# SIMCOM-SIM39EA-MALE.net
KiCad netlist of a schematic drawn in EAGLE
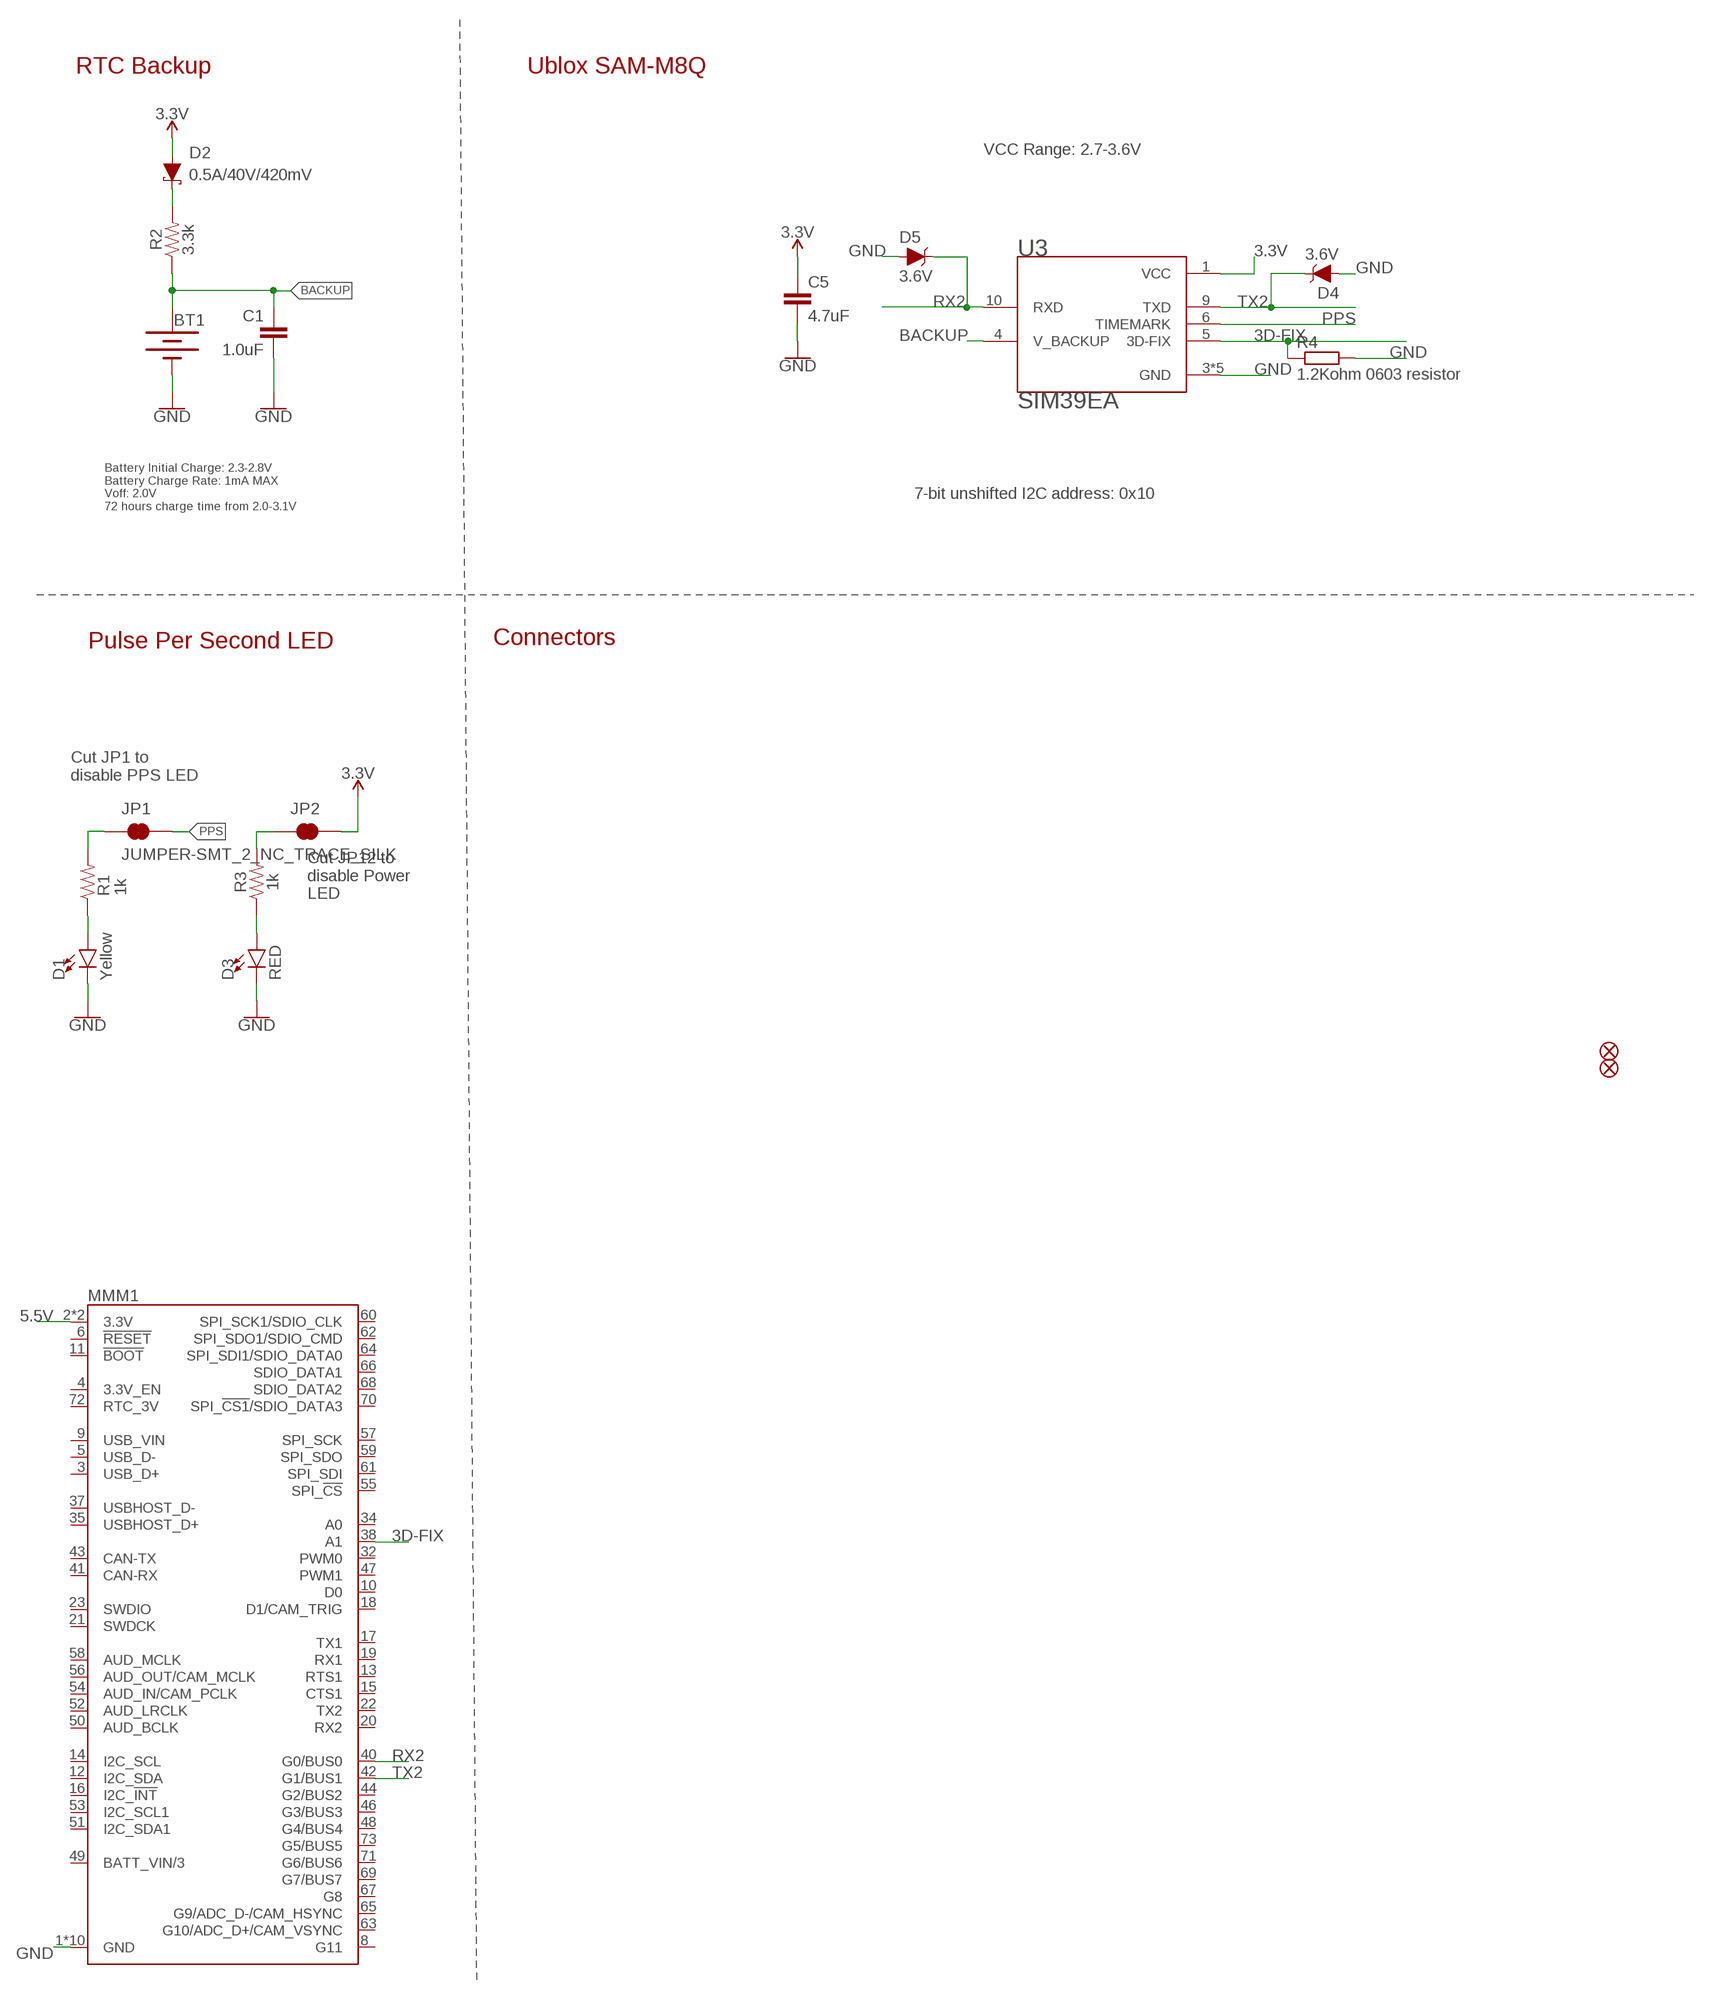
[diagram p0: schematic, sheet 1]
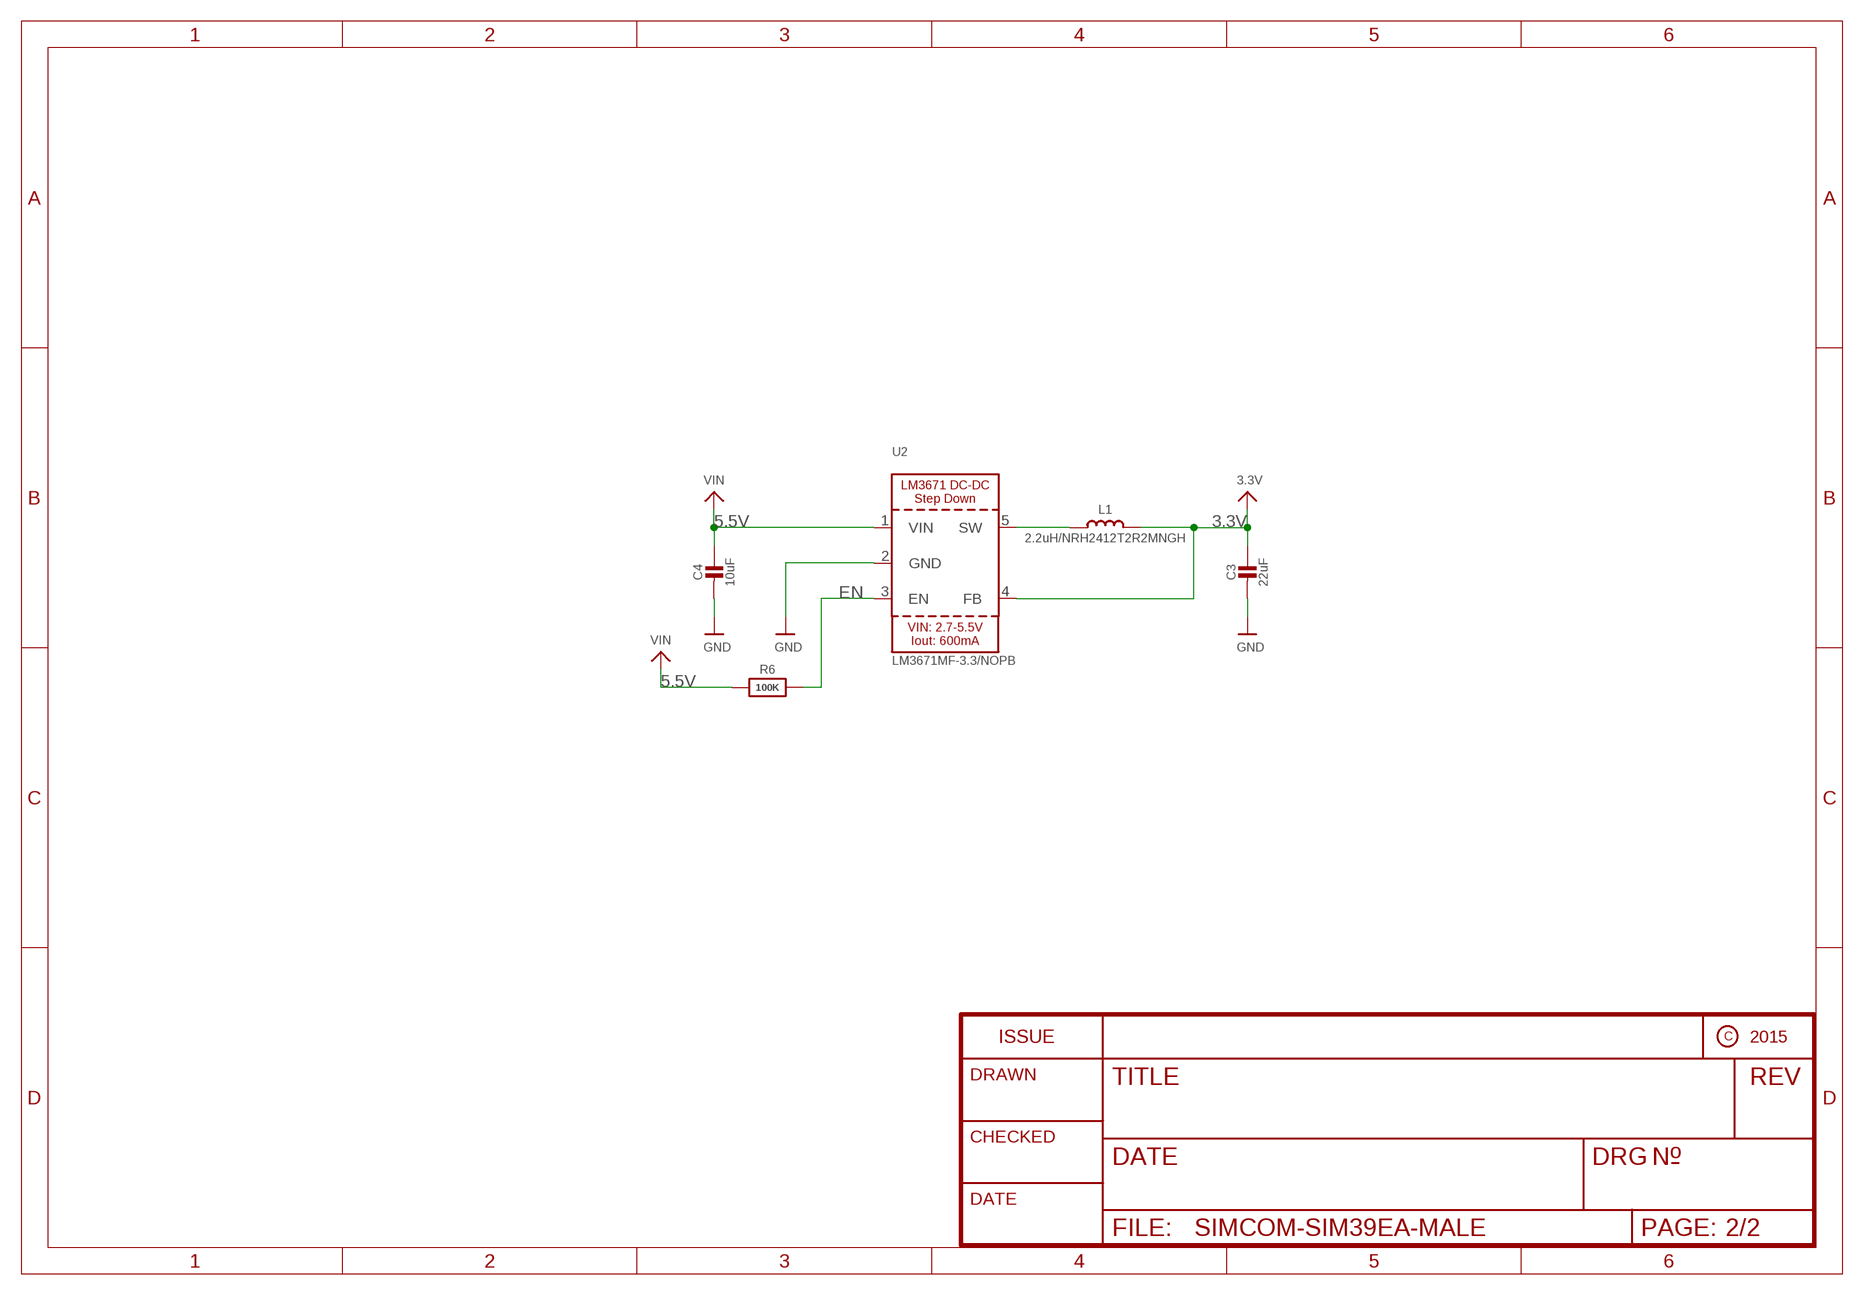
[diagram p1: schematic, sheet 2]

(export (version "E")
  (design (tool "Eeschema 10.0.6"))
  (components
    (comp (ref "BT1")
      (value "6.8MM_COIN_CELL")
      (footprint "eagle-import:ML414H_IV01E")
      (libsource (lib "eagle-import") (part "ML414H_IV01E_BATTERY"))
    )
    (comp (ref "C1")
      (value "1.0uF")
      (footprint "eagle-import:0603")
      (libsource (lib "eagle-import") (part "1.0UF-0603-16V-10%"))
    )
    (comp (ref "C5")
      (value "4.7uF")
      (footprint "eagle-import:0402-TIGHT")
      (libsource (lib "eagle-import") (part "4.7UF-0402_TIGHT-6.3V-20%-X5R"))
    )
    (comp (ref "D1")
      (value "Yellow")
      (footprint "eagle-import:LED-0603")
      (libsource (lib "eagle-import") (part "LED-YELLOW0603"))
    )
    (comp (ref "D2")
      (value "0.5A/40V/420mV")
      (footprint "eagle-import:SOD-323")
      (libsource (lib "eagle-import") (part "DIODE-SCHOTTKY-PMEG4005EJ"))
    )
    (comp (ref "D3")
      (value "RED")
      (footprint "eagle-import:LED-0603")
      (libsource (lib "eagle-import") (part "LED-RED0603"))
    )
    (comp (ref "D4")
      (value "3.6V")
      (footprint "eagle-import:SOD-323")
      (libsource (lib "eagle-import") (part "DIODE-ZENER-BZT52C3V6S"))
    )
    (comp (ref "D5")
      (value "3.6V")
      (footprint "eagle-import:SOD-323")
      (libsource (lib "eagle-import") (part "DIODE-ZENER-BZT52C3V6S"))
    )
    (comp (ref "FD3")
      (value "FIDUCIALUFIDUCIAL")
      (footprint "eagle-import:FIDUCIAL-MICRO")
      (libsource (lib "eagle-import") (part "FIDUCIALUFIDUCIAL"))
    )
    (comp (ref "FD4")
      (value "FIDUCIALUFIDUCIAL")
      (footprint "eagle-import:FIDUCIAL-MICRO")
      (libsource (lib "eagle-import") (part "FIDUCIALUFIDUCIAL"))
    )
    (comp (ref "JP1")
      (value "JUMPER-SMT_2_NC_TRACE_SILK")
      (footprint "eagle-import:SMT-JUMPER_2_NC_TRACE_SILK")
      (libsource (lib "eagle-import") (part "JUMPER-SMT_2_NC_TRACE_SILK"))
    )
    (comp (ref "JP2")
      (value "JUMPER-SMT_2_NC_TRACE_SILK")
      (footprint "eagle-import:SMT-JUMPER_2_NC_TRACE_SILK")
      (libsource (lib "eagle-import") (part "JUMPER-SMT_2_NC_TRACE_SILK"))
    )
    (comp (ref "MMM1")
      (value "MICROMOD_4222_MALE")
      (footprint "eagle-import:MICROMOD_4222_MALE")
      (libsource (lib "eagle-import") (part "MICROMOD_4222_MALE"))
    )
    (comp (ref "R1")
      (value "1k")
      (footprint "eagle-import:0603")
      (libsource (lib "eagle-import") (part "1KOHM-0603-1/10W-1%"))
    )
    (comp (ref "R2")
      (value "3.3k")
      (footprint "eagle-import:0603")
      (libsource (lib "eagle-import") (part "3.3KOHM-0603-1/10W-1%"))
    )
    (comp (ref "R3")
      (value "1k")
      (footprint "eagle-import:0603")
      (libsource (lib "eagle-import") (part "1KOHM-0603-1/10W-1%"))
    )
    (comp (ref "R4")
      (value "1.2Kohm 0603 resistor")
      (footprint "eagle-import:R603")
      (libsource (lib "eagle-import") (part "RESISTOR-0603"))
    )
    (comp (ref "U3")
      (value "SIM39EA")
      (footprint "eagle-import:DFN1600X1600X750-13N")
      (fields (field (name "MF") "Simcom"))
      (libsource (lib "eagle-import") (part "SIM39EA"))
    )
    (comp (ref "C3")
      (value "22uF")
      (footprint "eagle-import:0805-NO")
      (libsource (lib "eagle-import") (part "CAP_CERAMIC0805-NOOUTLINE"))
    )
    (comp (ref "C4")
      (value "10uF")
      (footprint "eagle-import:0805-NO")
      (libsource (lib "eagle-import") (part "CAP_CERAMIC0805-NOOUTLINE"))
    )
    (comp (ref "L1")
      (value "2.2uH/NRH2412T2R2MNGH")
      (footprint "eagle-import:INDUCTOR_TAIYOYUDEN_NRH2412T")
      (libsource (lib "eagle-import") (part "INDUCTORNRH2412T"))
    )
    (comp (ref "R6")
      (value "100K")
      (footprint "eagle-import:0805-NO")
      (libsource (lib "eagle-import") (part "RESISTOR0805_NOOUTLINE"))
    )
    (comp (ref "U2")
      (value "LM3671MF-3.3/NOPB")
      (footprint "eagle-import:SOT23-5")
      (libsource (lib "eagle-import") (part "VREG_LM3671"))
    )
  )
  (nets
    (net (code "1") (name "3.3V") (class "Default")
      (node (ref "C3") (pin "1") (pinfunction "1_1") (pintype "passive"))
      (node (ref "C5") (pin "1") (pinfunction "1_1") (pintype "passive"))
      (node (ref "D2") (pin "A") (pinfunction "A_A") (pintype "passive"))
      (node (ref "JP2") (pin "2") (pinfunction "2_2") (pintype "passive"))
      (node (ref "L1") (pin "2") (pinfunction "2_2") (pintype "passive"))
      (node (ref "U2") (pin "4") (pinfunction "FB_4") (pintype "power_in"))
      (node (ref "U3") (pin "1") (pinfunction "VCC_1") (pintype "power_in"))
    )
    (net (code "2") (name "3D-FIX") (class "Default")
      (node (ref "MMM1") (pin "38") (pinfunction "A1_38") (pintype "bidirectional"))
      (node (ref "R4") (pin "1") (pinfunction "1_1") (pintype "passive"))
      (node (ref "U3") (pin "5") (pinfunction "3D-FIX_5") (pintype "output"))
    )
    (net (code "3") (name "5.5V") (class "Default")
      (node (ref "C4") (pin "1") (pinfunction "1_1") (pintype "passive"))
      (node (ref "MMM1") (pin "2") (pinfunction "3.3V_2") (pintype "bidirectional"))
      (node (ref "MMM1") (pin "74") (pinfunction "3.3V_74") (pintype "bidirectional"))
      (node (ref "R6") (pin "1") (pinfunction "1_1") (pintype "passive"))
      (node (ref "U2") (pin "1") (pinfunction "VIN_1") (pintype "power_in"))
    )
    (net (code "4") (name "BACKUP") (class "Default")
      (node (ref "BT1") (pin "+") (pinfunction "+_+") (pintype "power_in"))
      (node (ref "C1") (pin "1") (pinfunction "1_1") (pintype "passive"))
      (node (ref "R2") (pin "1") (pinfunction "1_1") (pintype "passive"))
      (node (ref "U3") (pin "4") (pinfunction "V_BACKUP_4") (pintype "bidirectional"))
    )
    (net (code "5") (name "EN") (class "Default")
      (node (ref "R6") (pin "2") (pinfunction "2_2") (pintype "passive"))
      (node (ref "U2") (pin "3") (pinfunction "EN_3") (pintype "input"))
    )
    (net (code "6") (name "GND") (class "Default")
      (node (ref "BT1") (pin "-") (pinfunction "-_-") (pintype "power_in"))
      (node (ref "C1") (pin "2") (pinfunction "2_2") (pintype "passive"))
      (node (ref "C3") (pin "2") (pinfunction "2_2") (pintype "passive"))
      (node (ref "C4") (pin "2") (pinfunction "2_2") (pintype "passive"))
      (node (ref "C5") (pin "2") (pinfunction "2_2") (pintype "passive"))
      (node (ref "D1") (pin "C") (pinfunction "C_C") (pintype "passive"))
      (node (ref "D3") (pin "C") (pinfunction "C_C") (pintype "passive"))
      (node (ref "D4") (pin "A") (pinfunction "A_A") (pintype "passive"))
      (node (ref "D5") (pin "A") (pinfunction "A_A") (pintype "passive"))
      (node (ref "MMM1") (pin "1") (pinfunction "GND_1") (pintype "bidirectional"))
      (node (ref "MMM1") (pin "33") (pinfunction "GND_33") (pintype "bidirectional"))
      (node (ref "MMM1") (pin "36") (pinfunction "GND_36") (pintype "bidirectional"))
      (node (ref "MMM1") (pin "39") (pinfunction "GND_39") (pintype "bidirectional"))
      (node (ref "MMM1") (pin "45") (pinfunction "GND_45") (pintype "bidirectional"))
      (node (ref "MMM1") (pin "7") (pinfunction "GND_7") (pintype "bidirectional"))
      (node (ref "MMM1") (pin "75") (pinfunction "GND_75") (pintype "bidirectional"))
      (node (ref "MMM1") (pin "GND1") (pinfunction "GND_GND1") (pintype "bidirectional"))
      (node (ref "MMM1") (pin "GND2") (pinfunction "GND_GND2") (pintype "bidirectional"))
      (node (ref "MMM1") (pin "GND3") (pinfunction "GND_GND3") (pintype "bidirectional"))
      (node (ref "R4") (pin "2") (pinfunction "2_2") (pintype "passive"))
      (node (ref "U2") (pin "2") (pinfunction "GND_2") (pintype "power_in"))
      (node (ref "U3") (pin "11") (pinfunction "GND_11") (pintype "passive"))
      (node (ref "U3") (pin "12") (pinfunction "GND_12") (pintype "passive"))
      (node (ref "U3") (pin "13") (pinfunction "GND_13") (pintype "passive"))
      (node (ref "U3") (pin "3") (pinfunction "GND_3") (pintype "passive"))
      (node (ref "U3") (pin "8") (pinfunction "GND_8") (pintype "passive"))
    )
    (net (code "7") (name "Net-(D1-PadA)") (class "Default")
      (node (ref "D1") (pin "A") (pinfunction "A_A") (pintype "passive"))
      (node (ref "R1") (pin "1") (pinfunction "1_1") (pintype "passive"))
    )
    (net (code "8") (name "Net-(D2-PadC)") (class "Default")
      (node (ref "D2") (pin "C") (pinfunction "C_C") (pintype "passive"))
      (node (ref "R2") (pin "2") (pinfunction "2_2") (pintype "passive"))
    )
    (net (code "9") (name "Net-(D3-PadA)") (class "Default")
      (node (ref "D3") (pin "A") (pinfunction "A_A") (pintype "passive"))
      (node (ref "R3") (pin "1") (pinfunction "1_1") (pintype "passive"))
    )
    (net (code "10") (name "Net-(JP1-Pad1)") (class "Default")
      (node (ref "JP1") (pin "1") (pinfunction "1_1") (pintype "passive"))
      (node (ref "R1") (pin "2") (pinfunction "2_2") (pintype "passive"))
    )
    (net (code "11") (name "Net-(JP2-Pad1)") (class "Default")
      (node (ref "JP2") (pin "1") (pinfunction "1_1") (pintype "passive"))
      (node (ref "R3") (pin "2") (pinfunction "2_2") (pintype "passive"))
    )
    (net (code "12") (name "Net-(U2-SW)") (class "Default")
      (node (ref "L1") (pin "1") (pinfunction "1_1") (pintype "passive"))
      (node (ref "U2") (pin "5") (pinfunction "SW_5") (pintype "output"))
    )
    (net (code "13") (name "PPS") (class "Default")
      (node (ref "JP1") (pin "2") (pinfunction "2_2") (pintype "passive"))
      (node (ref "U3") (pin "6") (pinfunction "TIMEMARK_6") (pintype "output"))
    )
    (net (code "14") (name "RX2") (class "Default")
      (node (ref "D5") (pin "C") (pinfunction "C_C") (pintype "passive"))
      (node (ref "MMM1") (pin "40") (pinfunction "G0/BUS0_40") (pintype "bidirectional"))
      (node (ref "U3") (pin "10") (pinfunction "RXD_10") (pintype "input"))
    )
    (net (code "15") (name "TX2") (class "Default")
      (node (ref "D4") (pin "C") (pinfunction "C_C") (pintype "passive"))
      (node (ref "MMM1") (pin "42") (pinfunction "G1/BUS1_42") (pintype "bidirectional"))
      (node (ref "U3") (pin "9") (pinfunction "TXD_9") (pintype "output"))
    )
    (net (code "16") (name "unconnected-(MMM1-3.3V_EN-Pad4)") (class "Default")
      (node (ref "MMM1") (pin "4") (pinfunction "3.3V_EN_4") (pintype "bidirectional"))
    )
    (net (code "17") (name "unconnected-(MMM1-A0-Pad34)") (class "Default")
      (node (ref "MMM1") (pin "34") (pinfunction "A0_34") (pintype "bidirectional"))
    )
    (net (code "18") (name "unconnected-(MMM1-AUD_BCLK-Pad50)") (class "Default")
      (node (ref "MMM1") (pin "50") (pinfunction "AUD_BCLK_50") (pintype "bidirectional"))
    )
    (net (code "19") (name "unconnected-(MMM1-AUD_IN{slash}CAM_PCLK-Pad54)") (class "Default")
      (node (ref "MMM1") (pin "54") (pinfunction "AUD_IN/CAM_PCLK_54") (pintype "bidirectional"))
    )
    (net (code "20") (name "unconnected-(MMM1-AUD_LRCLK-Pad52)") (class "Default")
      (node (ref "MMM1") (pin "52") (pinfunction "AUD_LRCLK_52") (pintype "bidirectional"))
    )
    (net (code "21") (name "unconnected-(MMM1-AUD_MCLK-Pad58)") (class "Default")
      (node (ref "MMM1") (pin "58") (pinfunction "AUD_MCLK_58") (pintype "bidirectional"))
    )
    (net (code "22") (name "unconnected-(MMM1-AUD_OUT{slash}CAM_MCLK-Pad56)") (class "Default")
      (node (ref "MMM1") (pin "56") (pinfunction "AUD_OUT/CAM_MCLK_56") (pintype "bidirectional"))
    )
    (net (code "23") (name "unconnected-(MMM1-BATT_VIN{slash}3-Pad49)") (class "Default")
      (node (ref "MMM1") (pin "49") (pinfunction "BATT_VIN/3_49") (pintype "bidirectional"))
    )
    (net (code "24") (name "unconnected-(MMM1-CAN-RX-Pad41)") (class "Default")
      (node (ref "MMM1") (pin "41") (pinfunction "CAN-RX_41") (pintype "bidirectional"))
    )
    (net (code "25") (name "unconnected-(MMM1-CAN-TX-Pad43)") (class "Default")
      (node (ref "MMM1") (pin "43") (pinfunction "CAN-TX_43") (pintype "bidirectional"))
    )
    (net (code "26") (name "unconnected-(MMM1-CTS1-Pad15)") (class "Default")
      (node (ref "MMM1") (pin "15") (pinfunction "CTS1_15") (pintype "bidirectional"))
    )
    (net (code "27") (name "unconnected-(MMM1-D0-Pad10)") (class "Default")
      (node (ref "MMM1") (pin "10") (pinfunction "D0_10") (pintype "bidirectional"))
    )
    (net (code "28") (name "unconnected-(MMM1-D1{slash}CAM_TRIG-Pad18)") (class "Default")
      (node (ref "MMM1") (pin "18") (pinfunction "D1/CAM_TRIG_18") (pintype "bidirectional"))
    )
    (net (code "29") (name "unconnected-(MMM1-G2{slash}BUS2-Pad44)") (class "Default")
      (node (ref "MMM1") (pin "44") (pinfunction "G2/BUS2_44") (pintype "bidirectional"))
    )
    (net (code "30") (name "unconnected-(MMM1-G3{slash}BUS3-Pad46)") (class "Default")
      (node (ref "MMM1") (pin "46") (pinfunction "G3/BUS3_46") (pintype "bidirectional"))
    )
    (net (code "31") (name "unconnected-(MMM1-G4{slash}BUS4-Pad48)") (class "Default")
      (node (ref "MMM1") (pin "48") (pinfunction "G4/BUS4_48") (pintype "bidirectional"))
    )
    (net (code "32") (name "unconnected-(MMM1-G5{slash}BUS5-Pad73)") (class "Default")
      (node (ref "MMM1") (pin "73") (pinfunction "G5/BUS5_73") (pintype "bidirectional"))
    )
    (net (code "33") (name "unconnected-(MMM1-G6{slash}BUS6-Pad71)") (class "Default")
      (node (ref "MMM1") (pin "71") (pinfunction "G6/BUS6_71") (pintype "bidirectional"))
    )
    (net (code "34") (name "unconnected-(MMM1-G7{slash}BUS7-Pad69)") (class "Default")
      (node (ref "MMM1") (pin "69") (pinfunction "G7/BUS7_69") (pintype "bidirectional"))
    )
    (net (code "35") (name "unconnected-(MMM1-G8-Pad67)") (class "Default")
      (node (ref "MMM1") (pin "67") (pinfunction "G8_67") (pintype "bidirectional"))
    )
    (net (code "36") (name "unconnected-(MMM1-G9{slash}ADC_D-{slash}CAM_HSYNC-Pad65)") (class "Default")
      (node (ref "MMM1") (pin "65") (pinfunction "G9/ADC_D-/CAM_HSYNC_65") (pintype "bidirectional"))
    )
    (net (code "37") (name "unconnected-(MMM1-G10{slash}ADC_D+{slash}CAM_VSYNC-Pad63)") (class "Default")
      (node (ref "MMM1") (pin "63") (pinfunction "G10/ADC_D+/CAM_VSYNC_63") (pintype "bidirectional"))
    )
    (net (code "38") (name "unconnected-(MMM1-G11-Pad8)") (class "Default")
      (node (ref "MMM1") (pin "8") (pinfunction "G11_8") (pintype "bidirectional"))
    )
    (net (code "39") (name "unconnected-(MMM1-I2C_SCL-Pad14)") (class "Default")
      (node (ref "MMM1") (pin "14") (pinfunction "I2C_SCL_14") (pintype "bidirectional"))
    )
    (net (code "40") (name "unconnected-(MMM1-I2C_SCL1-Pad53)") (class "Default")
      (node (ref "MMM1") (pin "53") (pinfunction "I2C_SCL1_53") (pintype "bidirectional"))
    )
    (net (code "41") (name "unconnected-(MMM1-I2C_SDA-Pad12)") (class "Default")
      (node (ref "MMM1") (pin "12") (pinfunction "I2C_SDA_12") (pintype "bidirectional"))
    )
    (net (code "42") (name "unconnected-(MMM1-I2C_SDA1-Pad51)") (class "Default")
      (node (ref "MMM1") (pin "51") (pinfunction "I2C_SDA1_51") (pintype "bidirectional"))
    )
    (net (code "43") (name "unconnected-(MMM1-I2C_~{INT}-Pad16)") (class "Default")
      (node (ref "MMM1") (pin "16") (pinfunction "I2C_~{INT}_16") (pintype "bidirectional"))
    )
    (net (code "44") (name "unconnected-(MMM1-PWM0-Pad32)") (class "Default")
      (node (ref "MMM1") (pin "32") (pinfunction "PWM0_32") (pintype "bidirectional"))
    )
    (net (code "45") (name "unconnected-(MMM1-PWM1-Pad47)") (class "Default")
      (node (ref "MMM1") (pin "47") (pinfunction "PWM1_47") (pintype "bidirectional"))
    )
    (net (code "46") (name "unconnected-(MMM1-RTC_3V-Pad72)") (class "Default")
      (node (ref "MMM1") (pin "72") (pinfunction "RTC_3V_72") (pintype "bidirectional"))
    )
    (net (code "47") (name "unconnected-(MMM1-RTS1-Pad13)") (class "Default")
      (node (ref "MMM1") (pin "13") (pinfunction "RTS1_13") (pintype "bidirectional"))
    )
    (net (code "48") (name "unconnected-(MMM1-RX1-Pad19)") (class "Default")
      (node (ref "MMM1") (pin "19") (pinfunction "RX1_19") (pintype "bidirectional"))
    )
    (net (code "49") (name "unconnected-(MMM1-RX2-Pad20)") (class "Default")
      (node (ref "MMM1") (pin "20") (pinfunction "RX2_20") (pintype "bidirectional"))
    )
    (net (code "50") (name "unconnected-(MMM1-SDIO_DATA1-Pad66)") (class "Default")
      (node (ref "MMM1") (pin "66") (pinfunction "SDIO_DATA1_66") (pintype "bidirectional"))
    )
    (net (code "51") (name "unconnected-(MMM1-SDIO_DATA2-Pad68)") (class "Default")
      (node (ref "MMM1") (pin "68") (pinfunction "SDIO_DATA2_68") (pintype "bidirectional"))
    )
    (net (code "52") (name "unconnected-(MMM1-SPI_SCK-Pad57)") (class "Default")
      (node (ref "MMM1") (pin "57") (pinfunction "SPI_SCK_57") (pintype "bidirectional"))
    )
    (net (code "53") (name "unconnected-(MMM1-SPI_SCK1{slash}SDIO_CLK-Pad60)") (class "Default")
      (node (ref "MMM1") (pin "60") (pinfunction "SPI_SCK1/SDIO_CLK_60") (pintype "bidirectional"))
    )
    (net (code "54") (name "unconnected-(MMM1-SPI_SDI-Pad61)") (class "Default")
      (node (ref "MMM1") (pin "61") (pinfunction "SPI_SDI_61") (pintype "bidirectional"))
    )
    (net (code "55") (name "unconnected-(MMM1-SPI_SDI1{slash}SDIO_DATA0-Pad64)") (class "Default")
      (node (ref "MMM1") (pin "64") (pinfunction "SPI_SDI1/SDIO_DATA0_64") (pintype "bidirectional"))
    )
    (net (code "56") (name "unconnected-(MMM1-SPI_SDO-Pad59)") (class "Default")
      (node (ref "MMM1") (pin "59") (pinfunction "SPI_SDO_59") (pintype "bidirectional"))
    )
    (net (code "57") (name "unconnected-(MMM1-SPI_SDO1{slash}SDIO_CMD-Pad62)") (class "Default")
      (node (ref "MMM1") (pin "62") (pinfunction "SPI_SDO1/SDIO_CMD_62") (pintype "bidirectional"))
    )
    (net (code "58") (name "unconnected-(MMM1-SPI_~{CS1}{slash}SDIO_DATA3-Pad70)") (class "Default")
      (node (ref "MMM1") (pin "70") (pinfunction "SPI_~{CS1}/SDIO_DATA3_70") (pintype "bidirectional"))
    )
    (net (code "59") (name "unconnected-(MMM1-SPI_~{CS}-Pad55)") (class "Default")
      (node (ref "MMM1") (pin "55") (pinfunction "SPI_~{CS}_55") (pintype "bidirectional"))
    )
    (net (code "60") (name "unconnected-(MMM1-SWDCK-Pad21)") (class "Default")
      (node (ref "MMM1") (pin "21") (pinfunction "SWDCK_21") (pintype "bidirectional"))
    )
    (net (code "61") (name "unconnected-(MMM1-SWDIO-Pad23)") (class "Default")
      (node (ref "MMM1") (pin "23") (pinfunction "SWDIO_23") (pintype "bidirectional"))
    )
    (net (code "62") (name "unconnected-(MMM1-TX1-Pad17)") (class "Default")
      (node (ref "MMM1") (pin "17") (pinfunction "TX1_17") (pintype "bidirectional"))
    )
    (net (code "63") (name "unconnected-(MMM1-TX2-Pad22)") (class "Default")
      (node (ref "MMM1") (pin "22") (pinfunction "TX2_22") (pintype "bidirectional"))
    )
    (net (code "64") (name "unconnected-(MMM1-USBHOST_D+-Pad35)") (class "Default")
      (node (ref "MMM1") (pin "35") (pinfunction "USBHOST_D+_35") (pintype "bidirectional"))
    )
    (net (code "65") (name "unconnected-(MMM1-USBHOST_D--Pad37)") (class "Default")
      (node (ref "MMM1") (pin "37") (pinfunction "USBHOST_D-_37") (pintype "bidirectional"))
    )
    (net (code "66") (name "unconnected-(MMM1-USB_D+-Pad3)") (class "Default")
      (node (ref "MMM1") (pin "3") (pinfunction "USB_D+_3") (pintype "bidirectional"))
    )
    (net (code "67") (name "unconnected-(MMM1-USB_D--Pad5)") (class "Default")
      (node (ref "MMM1") (pin "5") (pinfunction "USB_D-_5") (pintype "bidirectional"))
    )
    (net (code "68") (name "unconnected-(MMM1-USB_VIN-Pad9)") (class "Default")
      (node (ref "MMM1") (pin "9") (pinfunction "USB_VIN_9") (pintype "bidirectional"))
    )
    (net (code "69") (name "unconnected-(MMM1-~{BOOT}-Pad11)") (class "Default")
      (node (ref "MMM1") (pin "11") (pinfunction "~{BOOT}_11") (pintype "bidirectional"))
    )
    (net (code "70") (name "unconnected-(MMM1-~{RESET}-Pad6)") (class "Default")
      (node (ref "MMM1") (pin "6") (pinfunction "~{RESET}_6") (pintype "bidirectional"))
    )
  )
)
